# pwr_supply.net
KiCad netlist of a schematic drawn in Altium Designer
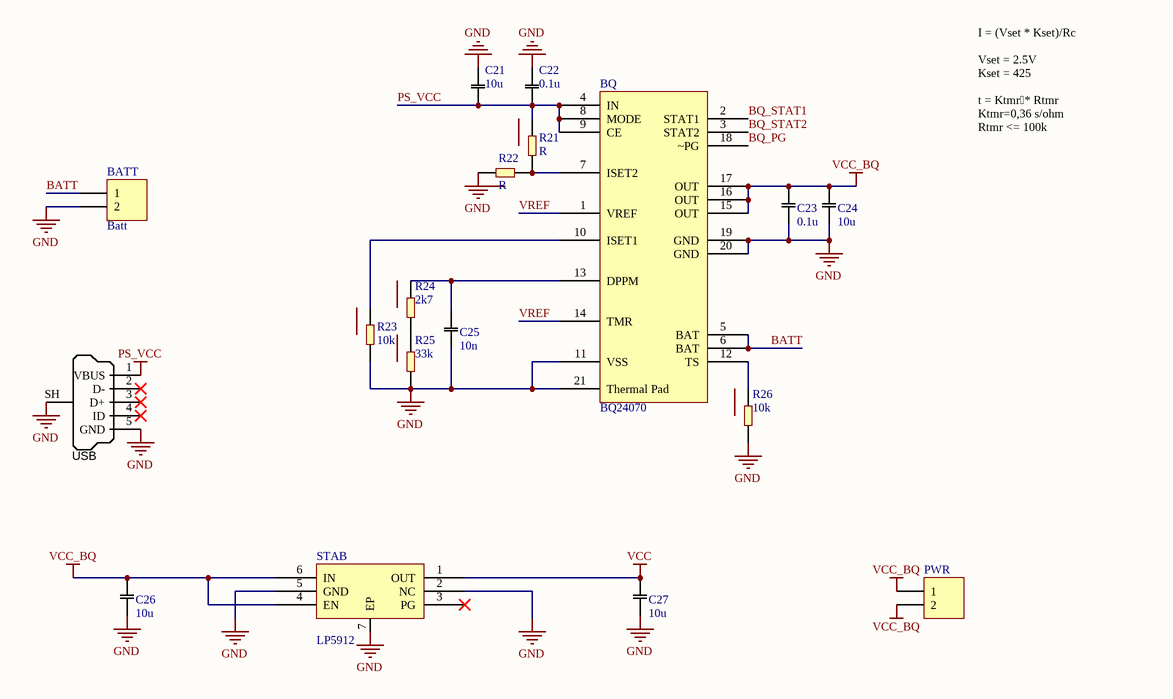
[diagram p0: pwr_supply.SchDoc]

(export (version "E")
  (design (tool "Eeschema 10.0.6"))
  (components
    (comp (ref "BATT")
      (value "Batt")
      (footprint "HDR1X2")
      (description "Header, 2-Pin")
      (fields (field (name "PUBLISHER") "Altium Limited"))
      (libsource (lib "Miscellaneous Connectors") (part "Header 2"))
    )
    (comp (ref "BQ") (value "BQ24070") (footprint "BQ24070") (libsource (lib "LoraLib") (part "BQ24070")))
    (comp (ref "C21")
      (value "10u")
      (footprint "603")
      (description "Capacitor")
      (libsource (lib "pass_comp") (part "C"))
    )
    (comp (ref "C22")
      (value "0.1u")
      (footprint "603")
      (description "Capacitor")
      (libsource (lib "pass_comp") (part "C"))
    )
    (comp (ref "C23")
      (value "0.1u")
      (footprint "603")
      (description "Capacitor")
      (libsource (lib "pass_comp") (part "C"))
    )
    (comp (ref "C24")
      (value "10u")
      (footprint "603")
      (description "Capacitor")
      (libsource (lib "pass_comp") (part "C"))
    )
    (comp (ref "C25")
      (value "10n")
      (footprint "603")
      (description "Capacitor")
      (libsource (lib "pass_comp") (part "C"))
    )
    (comp (ref "C26")
      (value "10u")
      (footprint "402")
      (description "Capacitor")
      (libsource (lib "pass_comp") (part "C"))
    )
    (comp (ref "C27")
      (value "10u")
      (footprint "402")
      (description "Capacitor")
      (libsource (lib "pass_comp") (part "C"))
    )
    (comp (ref "PWR")
      (value "~")
      (footprint "HDR1X2")
      (description "Header, 2-Pin")
      (fields (field (name "PUBLISHER") "Altium Limited"))
      (libsource (lib "Miscellaneous Connectors") (part "Header 2"))
    )
    (comp (ref "R21")
      (value "R")
      (footprint "603")
      (description "Resistor")
      (libsource (lib "pass_comp") (part "R"))
    )
    (comp (ref "R22")
      (value "R")
      (footprint "603")
      (description "Resistor")
      (libsource (lib "") (part "R_1"))
    )
    (comp (ref "R23")
      (value "10k")
      (footprint "603")
      (description "Resistor")
      (libsource (lib "pass_comp") (part "R"))
    )
    (comp (ref "R24")
      (value "2k7")
      (footprint "603")
      (description "Resistor")
      (libsource (lib "pass_comp") (part "R"))
    )
    (comp (ref "R25")
      (value "33k")
      (footprint "603")
      (description "Resistor")
      (libsource (lib "pass_comp") (part "R"))
    )
    (comp (ref "R26")
      (value "10k")
      (footprint "603")
      (description "Resistor")
      (libsource (lib "pass_comp") (part "R"))
    )
    (comp (ref "STAB") (value "LP5912") (footprint "WSON-6") (libsource (lib "env_sens") (part "LP5912")))
    (comp (ref "USB")
      (value "USB Micro Type B")
      (footprint "USB_Micro-B")
      (description "Connector SMD USB Micro Type B middle mount")
      (libsource (lib "env_sens") (part "USB_Micro_TypeB"))
    )
  )
  (nets
    (net (code "1") (name "/BATT") (class "Default")
      (node (ref "BATT") (pin "1") (pinfunction "1_1") (pintype "passive"))
      (node (ref "BQ") (pin "5") (pinfunction "BAT_5") (pintype "passive"))
      (node (ref "BQ") (pin "6") (pinfunction "BAT_6") (pintype "passive"))
    )
    (net (code "2") (name "/BQ_PG") (class "Default")
      (node (ref "BQ") (pin "18") (pinfunction "~PG_18") (pintype "passive"))
    )
    (net (code "3") (name "/BQ_STAT1") (class "Default")
      (node (ref "BQ") (pin "2") (pinfunction "STAT1_2") (pintype "passive"))
    )
    (net (code "4") (name "/BQ_STAT2") (class "Default")
      (node (ref "BQ") (pin "3") (pinfunction "STAT2_3") (pintype "passive"))
    )
    (net (code "5") (name "/VREF") (class "Default")
      (node (ref "BQ") (pin "1") (pinfunction "VREF_1") (pintype "passive"))
      (node (ref "BQ") (pin "14") (pinfunction "TMR_14") (pintype "passive"))
    )
    (net (code "6") (name "GND") (class "Default")
      (node (ref "BATT") (pin "2") (pinfunction "2_2") (pintype "passive"))
      (node (ref "BQ") (pin "11") (pinfunction "VSS_11") (pintype "passive"))
      (node (ref "BQ") (pin "19") (pinfunction "GND_19") (pintype "passive"))
      (node (ref "BQ") (pin "20") (pinfunction "GND_20") (pintype "passive"))
      (node (ref "BQ") (pin "21") (pinfunction "Thermal_Pad_21") (pintype "passive"))
      (node (ref "C21") (pin "2") (pintype "passive"))
      (node (ref "C22") (pin "2") (pintype "passive"))
      (node (ref "C23") (pin "1") (pintype "passive"))
      (node (ref "C24") (pin "1") (pintype "passive"))
      (node (ref "C25") (pin "1") (pintype "passive"))
      (node (ref "C26") (pin "1") (pintype "passive"))
      (node (ref "C27") (pin "1") (pintype "passive"))
      (node (ref "R22") (pin "2") (pintype "passive"))
      (node (ref "R23") (pin "1") (pintype "passive"))
      (node (ref "R25") (pin "1") (pintype "passive"))
      (node (ref "R26") (pin "1") (pintype "passive"))
      (node (ref "STAB") (pin "2") (pinfunction "NC_2") (pintype "passive"))
      (node (ref "STAB") (pin "5") (pinfunction "GND_5") (pintype "passive"))
      (node (ref "STAB") (pin "7") (pinfunction "EP_7") (pintype "passive"))
      (node (ref "USB") (pin "5") (pinfunction "GND_5") (pintype "passive"))
      (node (ref "USB") (pin "SH") (pinfunction "Shell_SH") (pintype "passive"))
    )
    (net (code "7") (name "Net-(BQ-DPPM)") (class "Default")
      (node (ref "BQ") (pin "13") (pinfunction "DPPM_13") (pintype "passive"))
      (node (ref "C25") (pin "2") (pintype "passive"))
      (node (ref "R24") (pin "2") (pintype "passive"))
    )
    (net (code "8") (name "Net-(BQ-ISET1)") (class "Default")
      (node (ref "BQ") (pin "10") (pinfunction "ISET1_10") (pintype "passive"))
      (node (ref "R23") (pin "2") (pintype "passive"))
    )
    (net (code "9") (name "Net-(BQ-ISET2)") (class "Default")
      (node (ref "BQ") (pin "7") (pinfunction "ISET2_7") (pintype "passive"))
      (node (ref "R21") (pin "1") (pintype "passive"))
      (node (ref "R22") (pin "1") (pintype "passive"))
    )
    (net (code "10") (name "Net-(BQ-TS)") (class "Default")
      (node (ref "BQ") (pin "12") (pinfunction "TS_12") (pintype "passive"))
      (node (ref "R26") (pin "2") (pintype "passive"))
    )
    (net (code "11") (name "Net-(R24-Pad1)") (class "Default")
      (node (ref "R24") (pin "1") (pintype "passive"))
      (node (ref "R25") (pin "2") (pintype "passive"))
    )
    (net (code "12") (name "PS_VCC") (class "Default")
      (node (ref "BQ") (pin "4") (pinfunction "IN_4") (pintype "passive"))
      (node (ref "BQ") (pin "8") (pinfunction "MODE_8") (pintype "passive"))
      (node (ref "BQ") (pin "9") (pinfunction "CE_9") (pintype "passive"))
      (node (ref "C21") (pin "1") (pintype "passive"))
      (node (ref "C22") (pin "1") (pintype "passive"))
      (node (ref "R21") (pin "2") (pintype "passive"))
      (node (ref "USB") (pin "1") (pinfunction "VBUS_1") (pintype "passive"))
    )
    (net (code "13") (name "VCC") (class "Default")
      (node (ref "C27") (pin "2") (pintype "passive"))
      (node (ref "STAB") (pin "1") (pinfunction "OUT_1") (pintype "passive"))
    )
    (net (code "14") (name "VCC_BQ") (class "Default")
      (node (ref "BQ") (pin "15") (pinfunction "OUT_15") (pintype "passive"))
      (node (ref "BQ") (pin "16") (pinfunction "OUT_16") (pintype "passive"))
      (node (ref "BQ") (pin "17") (pinfunction "OUT_17") (pintype "passive"))
      (node (ref "C23") (pin "2") (pintype "passive"))
      (node (ref "C24") (pin "2") (pintype "passive"))
      (node (ref "C26") (pin "2") (pintype "passive"))
      (node (ref "PWR") (pin "1") (pinfunction "1_1") (pintype "passive"))
      (node (ref "PWR") (pin "2") (pinfunction "2_2") (pintype "passive"))
      (node (ref "STAB") (pin "4") (pinfunction "EN_4") (pintype "passive"))
      (node (ref "STAB") (pin "6") (pinfunction "IN_6") (pintype "passive"))
    )
    (net (code "15") (name "unconnected-(STAB-PG-Pad3)") (class "Default")
      (node (ref "STAB") (pin "3") (pinfunction "PG_3") (pintype "passive+no_connect"))
    )
    (net (code "16") (name "unconnected-(USB-D+-Pad3)") (class "Default")
      (node (ref "USB") (pin "3") (pinfunction "D+_3") (pintype "passive+no_connect"))
    )
    (net (code "17") (name "unconnected-(USB-D--Pad2)") (class "Default")
      (node (ref "USB") (pin "2") (pinfunction "D-_2") (pintype "passive+no_connect"))
    )
    (net (code "18") (name "unconnected-(USB-ID-Pad4)") (class "Default")
      (node (ref "USB") (pin "4") (pinfunction "ID_4") (pintype "passive+no_connect"))
    )
  )
)
